# 05_LensControl.net
KiCad netlist of a schematic drawn in Altium Designer
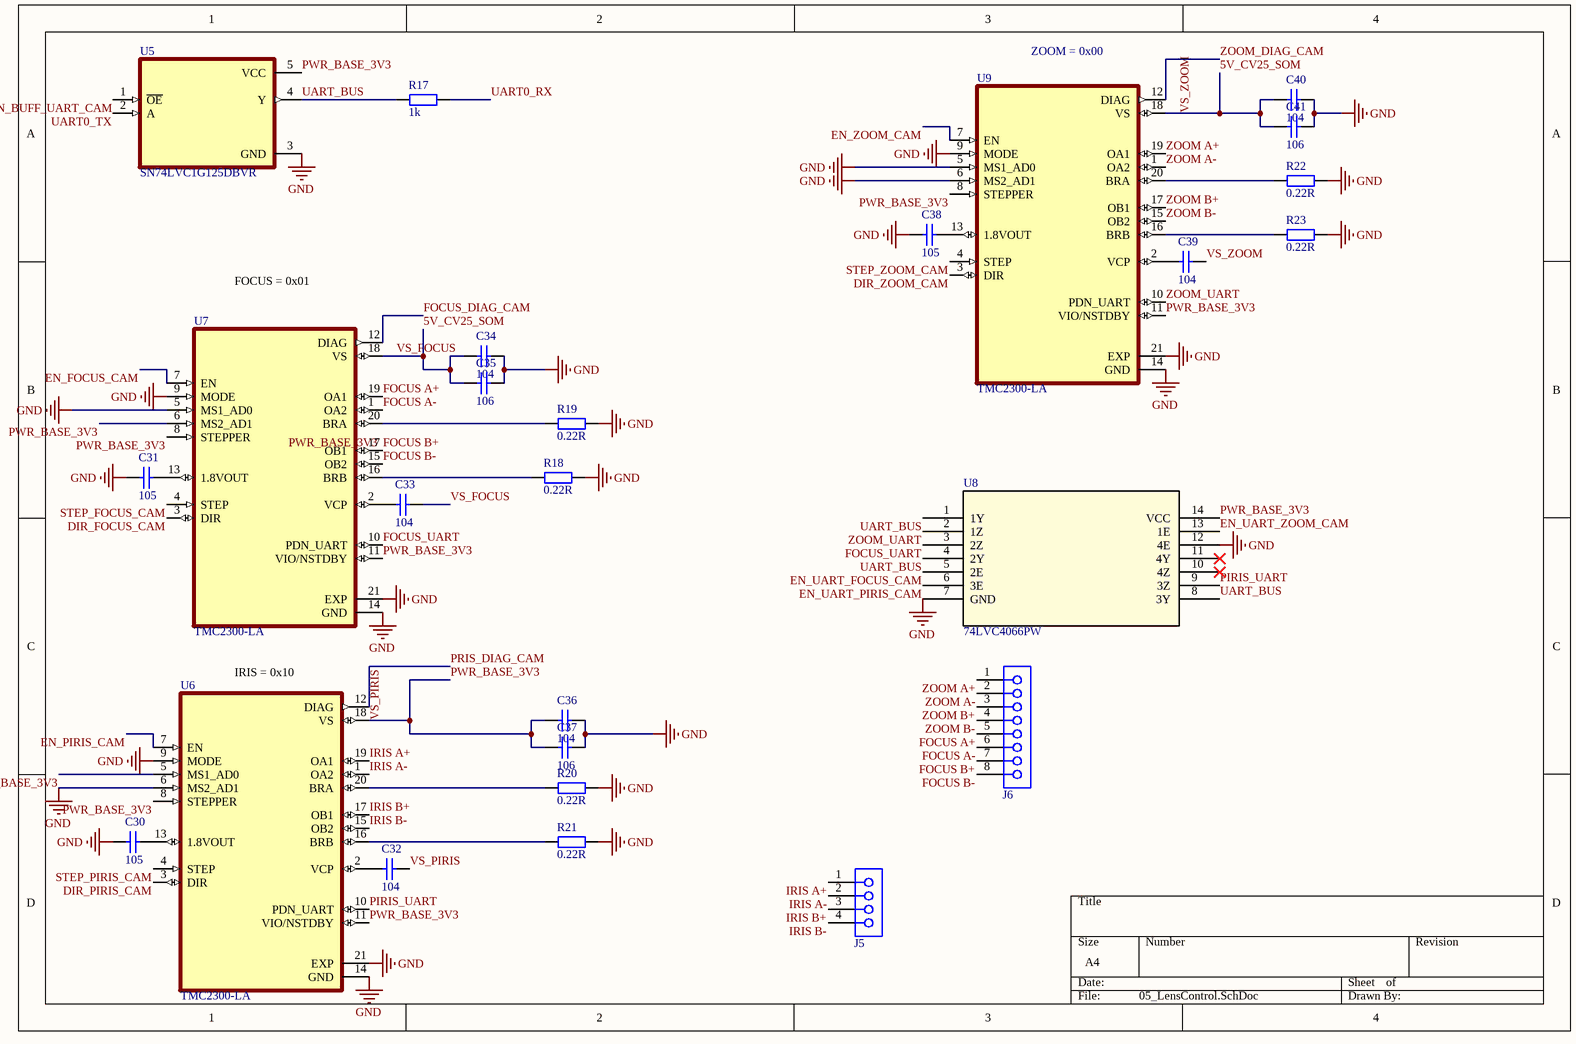
[diagram p0: 05_LensControl.SchDoc]

(export (version "E")
  (design (tool "Eeschema 10.0.6"))
  (components
    (comp (ref "C30")
      (value "105")
      (footprint "tu 0805")
      (description "Dán")
      (libsource (lib "Altium_Lib_by_KhueNguyenCreator") (part "Tu 0805 105 50V 10%"))
    )
    (comp (ref "C31")
      (value "105")
      (footprint "tu 0805")
      (description "Dán")
      (libsource (lib "Altium_Lib_by_KhueNguyenCreator") (part "Tu 0805 105 50V 10%"))
    )
    (comp (ref "C32")
      (value "104")
      (footprint "tu 1206")
      (description "Dán")
      (libsource (lib "Altium_Lib_by_KhueNguyenCreator") (part "Tu 1206 104 50V 20%"))
    )
    (comp (ref "C33")
      (value "104")
      (footprint "tu 1206")
      (description "Dán")
      (libsource (lib "Altium_Lib_by_KhueNguyenCreator") (part "Tu 1206 104 50V 20%"))
    )
    (comp (ref "C34")
      (value "104")
      (footprint "tu 1206")
      (description "Dán")
      (libsource (lib "Altium_Lib_by_KhueNguyenCreator") (part "Tu 1206 104 50V 20%"))
    )
    (comp (ref "C35")
      (value "106")
      (footprint "tu 0805")
      (description "Dán")
      (libsource (lib "Altium_Lib_by_KhueNguyenCreator") (part "Tu 0805 106 16V 10%"))
    )
    (comp (ref "C36")
      (value "104")
      (footprint "tu 1206")
      (description "Dán")
      (libsource (lib "Altium_Lib_by_KhueNguyenCreator") (part "Tu 1206 104 50V 20%"))
    )
    (comp (ref "C37")
      (value "106")
      (footprint "tu 0805")
      (description "Dán")
      (libsource (lib "Altium_Lib_by_KhueNguyenCreator") (part "Tu 0805 106 16V 10%"))
    )
    (comp (ref "C38")
      (value "105")
      (footprint "tu 0805")
      (description "Dán")
      (libsource (lib "Altium_Lib_by_KhueNguyenCreator") (part "Tu 0805 105 50V 10%"))
    )
    (comp (ref "C39")
      (value "104")
      (footprint "tu 1206")
      (description "Dán")
      (libsource (lib "Altium_Lib_by_KhueNguyenCreator") (part "Tu 1206 104 50V 20%"))
    )
    (comp (ref "C40")
      (value "104")
      (footprint "tu 1206")
      (description "Dán")
      (libsource (lib "Altium_Lib_by_KhueNguyenCreator") (part "Tu 1206 104 50V 20%"))
    )
    (comp (ref "C41")
      (value "106")
      (footprint "tu 0805")
      (description "Dán")
      (libsource (lib "Altium_Lib_by_KhueNguyenCreator") (part "Tu 0805 106 16V 10%"))
    )
    (comp (ref "J5")
      (value "61000411921")
      (footprint "61000411921")
      (description "WR-PHD Socket Header, SMT, Vertical, pitch 2.54mm, 1 Row, 4P")
      (fields (field (name "MANUFACTURER") "Wurth Elektronik"))
      (libsource (lib "Altium_WR-PHD_rev22b") (part "61000411921"))
    )
    (comp (ref "J6")
      (value "61000811921")
      (footprint "61000811921")
      (description "WR-PHD Socket Header, SMT, Vertical, pitch 2.54mm, 1 Row, 8P")
      (fields (field (name "MANUFACTURER") "Wurth Elektronik"))
      (libsource (lib "Altium_WR-PHD_rev22b") (part "61000811921"))
    )
    (comp (ref "R17")
      (value "1k")
      (footprint "tro smd 1206")
      (description "Dán")
      (libsource (lib "Altium_Lib_by_KhueNguyenCreator") (part "Tro 1206 1% 1k"))
    )
    (comp (ref "R18")
      (value "0.22R")
      (footprint "tro smd 0805")
      (description "Dán")
      (libsource (lib "Altium_Lib_by_KhueNguyenCreator") (part "Tro 0805 1% 0.22R"))
    )
    (comp (ref "R19")
      (value "0.22R")
      (footprint "tro smd 0805")
      (description "Dán")
      (libsource (lib "Altium_Lib_by_KhueNguyenCreator") (part "Tro 0805 1% 0.22R"))
    )
    (comp (ref "R20")
      (value "0.22R")
      (footprint "tro smd 0805")
      (description "Dán")
      (libsource (lib "Altium_Lib_by_KhueNguyenCreator") (part "Tro 0805 1% 0.22R"))
    )
    (comp (ref "R21")
      (value "0.22R")
      (footprint "tro smd 0805")
      (description "Dán")
      (libsource (lib "Altium_Lib_by_KhueNguyenCreator") (part "Tro 0805 1% 0.22R"))
    )
    (comp (ref "R22")
      (value "0.22R")
      (footprint "tro smd 0805")
      (description "Dán")
      (libsource (lib "Altium_Lib_by_KhueNguyenCreator") (part "Tro 0805 1% 0.22R"))
    )
    (comp (ref "R23")
      (value "0.22R")
      (footprint "tro smd 0805")
      (description "Dán")
      (libsource (lib "Altium_Lib_by_KhueNguyenCreator") (part "Tro 0805 1% 0.22R"))
    )
    (comp (ref "U5")
      (value "SN74LVC1G125DBVR")
      (footprint "SOT95P280X145-5N")
      (description "Single 1.65-V to 5.5-V buffer with 3-state outputs")
      (fields (field (name "MF") "Texas Instruments"))
      (libsource (lib "SN74LVC1G125DBVR") (part "SN74LVC1G125DBVR"))
    )
    (comp (ref "U6")
      (value "TMC2300-LA")
      (footprint "QFN40P300X300X90-21N")
      (description "Maxim Low Voltage Stepper Motor Driver IC, Step/Dir, UART, 2-11V Supply, 1.2A, QFN20")
      (fields (field (name "MF") "Maxim Integrated"))
      (libsource (lib "TMC2300-LA") (part "TMC2300-LA"))
    )
    (comp (ref "U7")
      (value "TMC2300-LA")
      (footprint "QFN40P300X300X90-21N")
      (description "Maxim Low Voltage Stepper Motor Driver IC, Step/Dir, UART, 2-11V Supply, 1.2A, QFN20")
      (fields (field (name "MF") "Maxim Integrated"))
      (libsource (lib "TMC2300-LA") (part "TMC2300-LA"))
    )
    (comp (ref "U8")
      (value "74LVC4066PW")
      (footprint "SOT402-1_NXP")
      (description "Description")
      (fields (field (name "COPYRIGHT") "Copyright (C) 2026 Ultra Librarian. All rights reserved."))
      (libsource (lib "74LVC4066PW") (part "74LVC4066PW"))
    )
    (comp (ref "U9")
      (value "TMC2300-LA")
      (footprint "QFN40P300X300X90-21N")
      (description "Maxim Low Voltage Stepper Motor Driver IC, Step/Dir, UART, 2-11V Supply, 1.2A, QFN20")
      (fields (field (name "MF") "Maxim Integrated"))
      (libsource (lib "TMC2300-LA") (part "TMC2300-LA"))
    )
  )
  (nets
    (net (code "1") (name "/5V_CV25_SOM") (class "Default")
      (node (ref "C33") (pin "2") (pinfunction "2_2") (pintype "passive"))
      (node (ref "C34") (pin "2") (pinfunction "2_2") (pintype "passive"))
      (node (ref "C35") (pin "2") (pinfunction "2_2") (pintype "passive"))
      (node (ref "C39") (pin "2") (pinfunction "2_2") (pintype "passive"))
      (node (ref "C40") (pin "2") (pinfunction "2_2") (pintype "passive"))
      (node (ref "C41") (pin "2") (pinfunction "2_2") (pintype "passive"))
      (node (ref "U7") (pin "18") (pinfunction "VS_18") (pintype "bidirectional"))
      (node (ref "U9") (pin "18") (pinfunction "VS_18") (pintype "bidirectional"))
    )
    (net (code "2") (name "/DIR_FOCUS_CAM") (class "Default")
      (node (ref "U7") (pin "3") (pinfunction "DIR_3") (pintype "bidirectional"))
    )
    (net (code "3") (name "/DIR_PIRIS_CAM") (class "Default")
      (node (ref "U6") (pin "3") (pinfunction "DIR_3") (pintype "bidirectional"))
    )
    (net (code "4") (name "/DIR_ZOOM_CAM") (class "Default")
      (node (ref "U9") (pin "3") (pinfunction "DIR_3") (pintype "bidirectional"))
    )
    (net (code "5") (name "/EN_BUFF_UART_CAM") (class "Default")
      (node (ref "U5") (pin "1") (pinfunction "~{OE}_1") (pintype "input"))
    )
    (net (code "6") (name "/EN_FOCUS_CAM") (class "Default")
      (node (ref "U7") (pin "7") (pinfunction "EN_7") (pintype "input"))
    )
    (net (code "7") (name "/EN_PIRIS_CAM") (class "Default")
      (node (ref "U6") (pin "7") (pinfunction "EN_7") (pintype "input"))
    )
    (net (code "8") (name "/EN_UART_FOCUS_CAM") (class "Default")
      (node (ref "U8") (pin "5") (pinfunction "2E_5") (pintype "passive"))
    )
    (net (code "9") (name "/EN_UART_PIRIS_CAM") (class "Default")
      (node (ref "U8") (pin "6") (pinfunction "3E_6") (pintype "passive"))
    )
    (net (code "10") (name "/EN_UART_ZOOM_CAM") (class "Default")
      (node (ref "U8") (pin "13") (pinfunction "1E_13") (pintype "passive"))
    )
    (net (code "11") (name "/EN_ZOOM_CAM") (class "Default")
      (node (ref "U9") (pin "7") (pinfunction "EN_7") (pintype "input"))
    )
    (net (code "12") (name "/FOCUS A+") (class "Default")
      (node (ref "J6") (pin "5") (pinfunction "5_5") (pintype "passive"))
      (node (ref "U7") (pin "19") (pinfunction "OA1_19") (pintype "bidirectional"))
    )
    (net (code "13") (name "/FOCUS A-") (class "Default")
      (node (ref "J6") (pin "6") (pinfunction "6_6") (pintype "passive"))
      (node (ref "U7") (pin "1") (pinfunction "OA2_1") (pintype "bidirectional"))
    )
    (net (code "14") (name "/FOCUS B+") (class "Default")
      (node (ref "J6") (pin "7") (pinfunction "7_7") (pintype "passive"))
      (node (ref "U7") (pin "17") (pinfunction "OB1_17") (pintype "bidirectional"))
    )
    (net (code "15") (name "/FOCUS B-") (class "Default")
      (node (ref "J6") (pin "8") (pinfunction "8_8") (pintype "passive"))
      (node (ref "U7") (pin "15") (pinfunction "OB2_15") (pintype "bidirectional"))
    )
    (net (code "16") (name "/FOCUS_DIAG_CAM") (class "Default")
      (node (ref "U7") (pin "12") (pinfunction "DIAG_12") (pintype "output"))
    )
    (net (code "17") (name "/FOCUS_UART") (class "Default")
      (node (ref "U7") (pin "10") (pinfunction "PDN_UART_10") (pintype "bidirectional"))
      (node (ref "U8") (pin "3") (pinfunction "2Z_3") (pintype "passive"))
    )
    (net (code "18") (name "/IRIS A+") (class "Default")
      (node (ref "J5") (pin "1") (pinfunction "1_1") (pintype "passive"))
      (node (ref "U6") (pin "19") (pinfunction "OA1_19") (pintype "bidirectional"))
    )
    (net (code "19") (name "/IRIS A-") (class "Default")
      (node (ref "J5") (pin "2") (pinfunction "2_2") (pintype "passive"))
      (node (ref "U6") (pin "1") (pinfunction "OA2_1") (pintype "bidirectional"))
    )
    (net (code "20") (name "/IRIS B+") (class "Default")
      (node (ref "J5") (pin "3") (pinfunction "3_3") (pintype "passive"))
      (node (ref "U6") (pin "17") (pinfunction "OB1_17") (pintype "bidirectional"))
    )
    (net (code "21") (name "/IRIS B-") (class "Default")
      (node (ref "J5") (pin "4") (pinfunction "4_4") (pintype "passive"))
      (node (ref "U6") (pin "15") (pinfunction "OB2_15") (pintype "bidirectional"))
    )
    (net (code "22") (name "/PIRIS_UART") (class "Default")
      (node (ref "U6") (pin "10") (pinfunction "PDN_UART_10") (pintype "bidirectional"))
      (node (ref "U8") (pin "9") (pinfunction "3Z_9") (pintype "passive"))
    )
    (net (code "23") (name "/PRIS_DIAG_CAM") (class "Default")
      (node (ref "U6") (pin "12") (pinfunction "DIAG_12") (pintype "output"))
    )
    (net (code "24") (name "/PWR_BASE_3V3") (class "Default")
      (node (ref "C32") (pin "2") (pinfunction "2_2") (pintype "passive"))
      (node (ref "C36") (pin "2") (pinfunction "2_2") (pintype "passive"))
      (node (ref "C37") (pin "2") (pinfunction "2_2") (pintype "passive"))
      (node (ref "U5") (pin "5") (pinfunction "VCC_5") (pintype "power_in"))
      (node (ref "U6") (pin "11") (pinfunction "VIO/NSTDBY_11") (pintype "bidirectional"))
      (node (ref "U6") (pin "18") (pinfunction "VS_18") (pintype "bidirectional"))
      (node (ref "U6") (pin "5") (pinfunction "MS1_AD0_5") (pintype "input"))
      (node (ref "U6") (pin "8") (pinfunction "STEPPER_8") (pintype "input"))
      (node (ref "U7") (pin "11") (pinfunction "VIO/NSTDBY_11") (pintype "bidirectional"))
      (node (ref "U7") (pin "6") (pinfunction "MS2_AD1_6") (pintype "input"))
      (node (ref "U7") (pin "8") (pinfunction "STEPPER_8") (pintype "input"))
      (node (ref "U8") (pin "14") (pinfunction "VCC_14") (pintype "passive"))
      (node (ref "U9") (pin "11") (pinfunction "VIO/NSTDBY_11") (pintype "bidirectional"))
      (node (ref "U9") (pin "8") (pinfunction "STEPPER_8") (pintype "input"))
    )
    (net (code "25") (name "/STEP_FOCUS_CAM") (class "Default")
      (node (ref "U7") (pin "4") (pinfunction "STEP_4") (pintype "input"))
    )
    (net (code "26") (name "/STEP_PIRIS_CAM") (class "Default")
      (node (ref "U6") (pin "4") (pinfunction "STEP_4") (pintype "input"))
    )
    (net (code "27") (name "/STEP_ZOOM_CAM") (class "Default")
      (node (ref "U9") (pin "4") (pinfunction "STEP_4") (pintype "input"))
    )
    (net (code "28") (name "/UART0_RX") (class "Default")
      (node (ref "R17") (pin "2") (pinfunction "2_2") (pintype "passive"))
    )
    (net (code "29") (name "/UART0_TX") (class "Default")
      (node (ref "U5") (pin "2") (pinfunction "A_2") (pintype "input"))
    )
    (net (code "30") (name "/UART_BUS") (class "Default")
      (node (ref "R17") (pin "1") (pinfunction "1_1") (pintype "passive"))
      (node (ref "U5") (pin "4") (pinfunction "Y_4") (pintype "output"))
      (node (ref "U8") (pin "1") (pinfunction "1Y_1") (pintype "passive"))
      (node (ref "U8") (pin "4") (pinfunction "2Y_4") (pintype "passive"))
      (node (ref "U8") (pin "8") (pinfunction "3Y_8") (pintype "passive"))
    )
    (net (code "31") (name "/ZOOM A+") (class "Default")
      (node (ref "J6") (pin "1") (pinfunction "1_1") (pintype "passive"))
      (node (ref "U9") (pin "19") (pinfunction "OA1_19") (pintype "bidirectional"))
    )
    (net (code "32") (name "/ZOOM A-") (class "Default")
      (node (ref "J6") (pin "2") (pinfunction "2_2") (pintype "passive"))
      (node (ref "U9") (pin "1") (pinfunction "OA2_1") (pintype "bidirectional"))
    )
    (net (code "33") (name "/ZOOM B+") (class "Default")
      (node (ref "J6") (pin "3") (pinfunction "3_3") (pintype "passive"))
      (node (ref "U9") (pin "17") (pinfunction "OB1_17") (pintype "bidirectional"))
    )
    (net (code "34") (name "/ZOOM B-") (class "Default")
      (node (ref "J6") (pin "4") (pinfunction "4_4") (pintype "passive"))
      (node (ref "U9") (pin "15") (pinfunction "OB2_15") (pintype "bidirectional"))
    )
    (net (code "35") (name "/ZOOM_DIAG_CAM") (class "Default")
      (node (ref "U9") (pin "12") (pinfunction "DIAG_12") (pintype "output"))
    )
    (net (code "36") (name "/ZOOM_UART") (class "Default")
      (node (ref "U8") (pin "2") (pinfunction "1Z_2") (pintype "passive"))
      (node (ref "U9") (pin "10") (pinfunction "PDN_UART_10") (pintype "bidirectional"))
    )
    (net (code "37") (name "GND") (class "Default")
      (node (ref "C30") (pin "2") (pinfunction "2_2") (pintype "passive"))
      (node (ref "C31") (pin "2") (pinfunction "2_2") (pintype "passive"))
      (node (ref "C34") (pin "1") (pinfunction "1_1") (pintype "passive"))
      (node (ref "C35") (pin "1") (pinfunction "1_1") (pintype "passive"))
      (node (ref "C36") (pin "1") (pinfunction "1_1") (pintype "passive"))
      (node (ref "C37") (pin "1") (pinfunction "1_1") (pintype "passive"))
      (node (ref "C38") (pin "2") (pinfunction "2_2") (pintype "passive"))
      (node (ref "C40") (pin "1") (pinfunction "1_1") (pintype "passive"))
      (node (ref "C41") (pin "1") (pinfunction "1_1") (pintype "passive"))
      (node (ref "R18") (pin "2") (pinfunction "2_2") (pintype "passive"))
      (node (ref "R19") (pin "2") (pinfunction "2_2") (pintype "passive"))
      (node (ref "R20") (pin "2") (pinfunction "2_2") (pintype "passive"))
      (node (ref "R21") (pin "2") (pinfunction "2_2") (pintype "passive"))
      (node (ref "R22") (pin "2") (pinfunction "2_2") (pintype "passive"))
      (node (ref "R23") (pin "2") (pinfunction "2_2") (pintype "passive"))
      (node (ref "U5") (pin "3") (pinfunction "GND_3") (pintype "power_in"))
      (node (ref "U6") (pin "14") (pinfunction "GND_14") (pintype "power_in"))
      (node (ref "U6") (pin "21") (pinfunction "EXP_21") (pintype "power_in"))
      (node (ref "U6") (pin "6") (pinfunction "MS2_AD1_6") (pintype "input"))
      (node (ref "U6") (pin "9") (pinfunction "MODE_9") (pintype "input"))
      (node (ref "U7") (pin "14") (pinfunction "GND_14") (pintype "power_in"))
      (node (ref "U7") (pin "21") (pinfunction "EXP_21") (pintype "power_in"))
      (node (ref "U7") (pin "5") (pinfunction "MS1_AD0_5") (pintype "input"))
      (node (ref "U7") (pin "9") (pinfunction "MODE_9") (pintype "input"))
      (node (ref "U8") (pin "12") (pinfunction "4E_12") (pintype "passive"))
      (node (ref "U8") (pin "7") (pinfunction "GND_7") (pintype "passive"))
      (node (ref "U9") (pin "14") (pinfunction "GND_14") (pintype "power_in"))
      (node (ref "U9") (pin "21") (pinfunction "EXP_21") (pintype "power_in"))
      (node (ref "U9") (pin "5") (pinfunction "MS1_AD0_5") (pintype "input"))
      (node (ref "U9") (pin "6") (pinfunction "MS2_AD1_6") (pintype "input"))
      (node (ref "U9") (pin "9") (pinfunction "MODE_9") (pintype "input"))
    )
    (net (code "38") (name "Net-(U6-1.8VOUT)") (class "Default")
      (node (ref "C30") (pin "1") (pinfunction "1_1") (pintype "passive"))
      (node (ref "U6") (pin "13") (pinfunction "1.8VOUT_13") (pintype "bidirectional"))
    )
    (net (code "39") (name "Net-(U6-BRA)") (class "Default")
      (node (ref "R20") (pin "1") (pinfunction "1_1") (pintype "passive"))
      (node (ref "U6") (pin "20") (pinfunction "BRA_20") (pintype "bidirectional"))
    )
    (net (code "40") (name "Net-(U6-BRB)") (class "Default")
      (node (ref "R21") (pin "1") (pinfunction "1_1") (pintype "passive"))
      (node (ref "U6") (pin "16") (pinfunction "BRB_16") (pintype "bidirectional"))
    )
    (net (code "41") (name "Net-(U6-VCP)") (class "Default")
      (node (ref "C32") (pin "1") (pinfunction "1_1") (pintype "passive"))
      (node (ref "U6") (pin "2") (pinfunction "VCP_2") (pintype "bidirectional"))
    )
    (net (code "42") (name "Net-(U7-1.8VOUT)") (class "Default")
      (node (ref "C31") (pin "1") (pinfunction "1_1") (pintype "passive"))
      (node (ref "U7") (pin "13") (pinfunction "1.8VOUT_13") (pintype "bidirectional"))
    )
    (net (code "43") (name "Net-(U7-BRA)") (class "Default")
      (node (ref "R19") (pin "1") (pinfunction "1_1") (pintype "passive"))
      (node (ref "U7") (pin "20") (pinfunction "BRA_20") (pintype "bidirectional"))
    )
    (net (code "44") (name "Net-(U7-BRB)") (class "Default")
      (node (ref "R18") (pin "1") (pinfunction "1_1") (pintype "passive"))
      (node (ref "U7") (pin "16") (pinfunction "BRB_16") (pintype "bidirectional"))
    )
    (net (code "45") (name "Net-(U7-VCP)") (class "Default")
      (node (ref "C33") (pin "1") (pinfunction "1_1") (pintype "passive"))
      (node (ref "U7") (pin "2") (pinfunction "VCP_2") (pintype "bidirectional"))
    )
    (net (code "46") (name "Net-(U9-1.8VOUT)") (class "Default")
      (node (ref "C38") (pin "1") (pinfunction "1_1") (pintype "passive"))
      (node (ref "U9") (pin "13") (pinfunction "1.8VOUT_13") (pintype "bidirectional"))
    )
    (net (code "47") (name "Net-(U9-BRA)") (class "Default")
      (node (ref "R22") (pin "1") (pinfunction "1_1") (pintype "passive"))
      (node (ref "U9") (pin "20") (pinfunction "BRA_20") (pintype "bidirectional"))
    )
    (net (code "48") (name "Net-(U9-BRB)") (class "Default")
      (node (ref "R23") (pin "1") (pinfunction "1_1") (pintype "passive"))
      (node (ref "U9") (pin "16") (pinfunction "BRB_16") (pintype "bidirectional"))
    )
    (net (code "49") (name "Net-(U9-VCP)") (class "Default")
      (node (ref "C39") (pin "1") (pinfunction "1_1") (pintype "passive"))
      (node (ref "U9") (pin "2") (pinfunction "VCP_2") (pintype "bidirectional"))
    )
    (net (code "50") (name "unconnected-(U8-4Y-Pad11)") (class "Default")
      (node (ref "U8") (pin "11") (pinfunction "4Y_11") (pintype "passive+no_connect"))
    )
    (net (code "51") (name "unconnected-(U8-4Z-Pad10)") (class "Default")
      (node (ref "U8") (pin "10") (pinfunction "4Z_10") (pintype "passive+no_connect"))
    )
  )
)
